# INTAN_Interface.net
KiCad netlist of a schematic drawn in Altium Designer
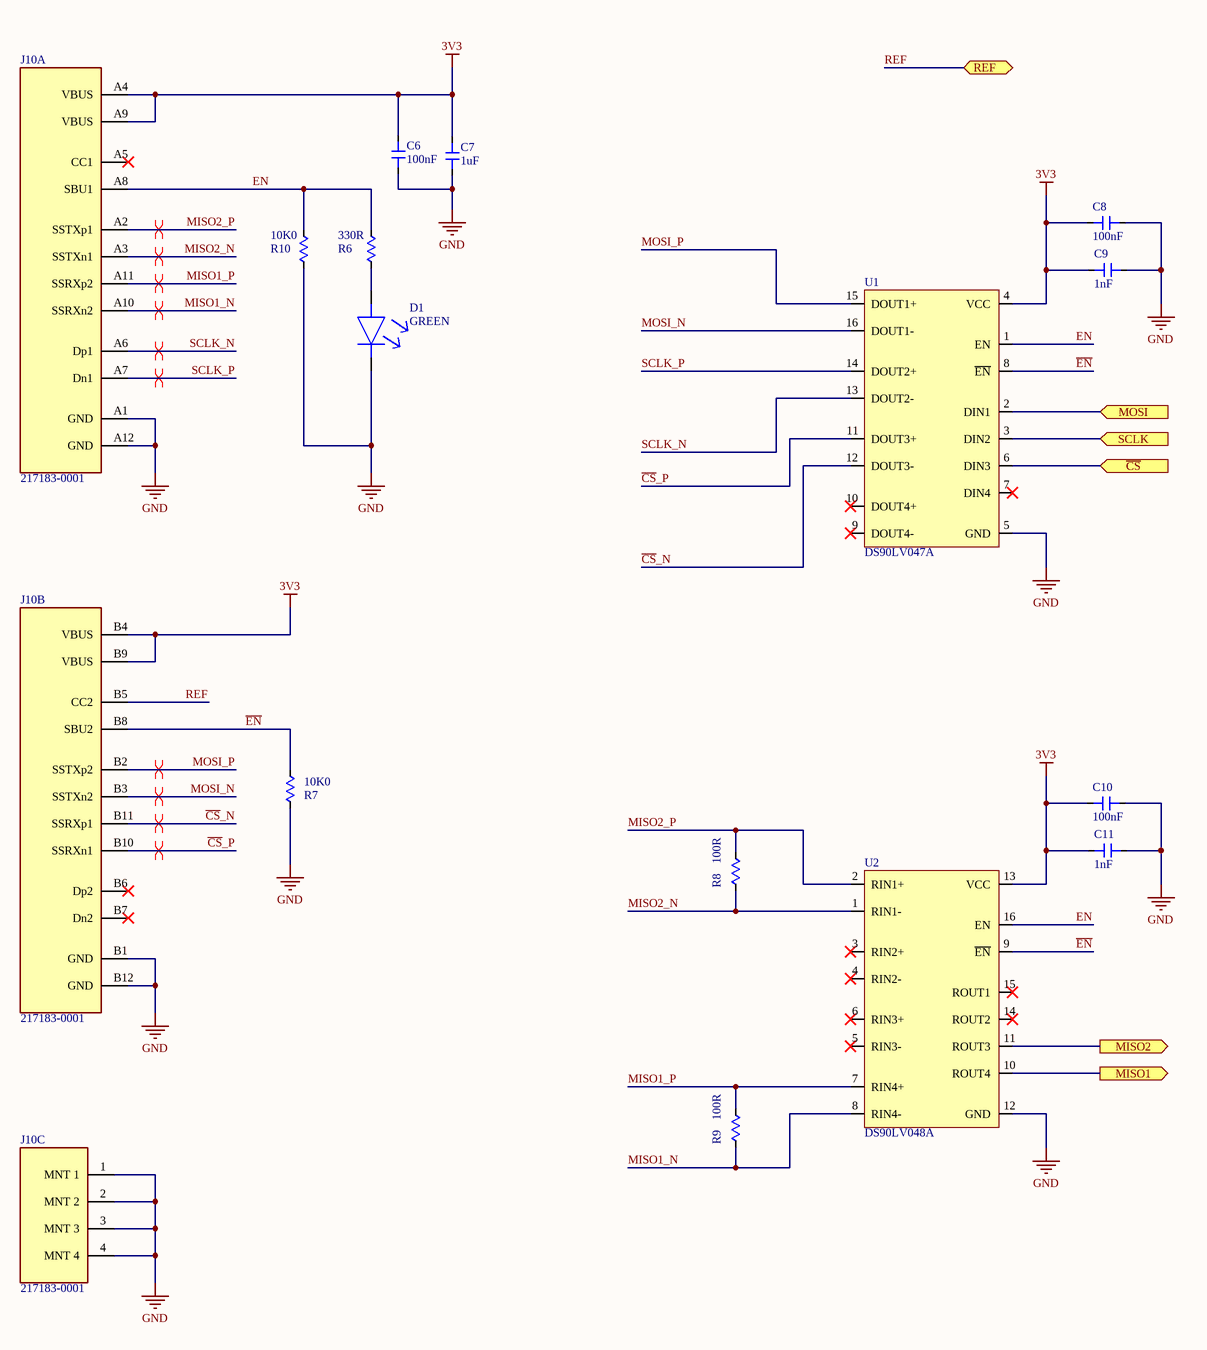
[diagram p0: INTAN_Interface.SchDoc]

(export (version "E")
  (design (tool "Eeschema 10.0.6"))
  (components
    (comp (ref "C6")
      (value "100nF")
      (footprint "0603_CAPACITOR")
      (description "Capacitor")
      (libsource (lib "UHDEMG") (part "Capacitor"))
    )
    (comp (ref "C7")
      (value "1uF")
      (footprint "0603_CAPACITOR")
      (description "Capacitor")
      (libsource (lib "UHDEMG") (part "Capacitor"))
    )
    (comp (ref "C8")
      (value "100nF")
      (footprint "0603_CAPACITOR")
      (description "Capacitor")
      (libsource (lib "UHDEMG") (part "Capacitor"))
    )
    (comp (ref "C9")
      (value "1nF")
      (footprint "0603_CAPACITOR")
      (description "Capacitor")
      (libsource (lib "UHDEMG") (part "Capacitor"))
    )
    (comp (ref "C10")
      (value "100nF")
      (footprint "0603_CAPACITOR")
      (description "Capacitor")
      (libsource (lib "UHDEMG") (part "Capacitor"))
    )
    (comp (ref "C11")
      (value "1nF")
      (footprint "0603_CAPACITOR")
      (description "Capacitor")
      (libsource (lib "UHDEMG") (part "Capacitor"))
    )
    (comp (ref "D1")
      (value "GREEN")
      (footprint "LED_APT1608LZGCK")
      (description "GREEN LED")
      (libsource (lib "UHDEMG") (part "LED_GREEN"))
    )
    (comp (ref "J10")
      (value "217183-0001")
      (footprint "CON_USB_C_SMD")
      (libsource (lib "UHDEMG") (part "CON_USBC_TH_SMT"))
    )
    (comp (ref "R6")
      (value "330R")
      (footprint "0603_RESISTOR")
      (description "Resistor")
      (libsource (lib "UHDEMG") (part "Resistor"))
    )
    (comp (ref "R7")
      (value "10K0")
      (footprint "0603_RESISTOR")
      (description "Resistor")
      (libsource (lib "UHDEMG") (part "Resistor"))
    )
    (comp (ref "R8")
      (value "100R")
      (footprint "0402_Resistor")
      (description "Resistor")
      (libsource (lib "UHDEMG") (part "Resistor"))
    )
    (comp (ref "R9")
      (value "100R")
      (footprint "0402_Resistor")
      (description "Resistor")
      (libsource (lib "UHDEMG") (part "Resistor"))
    )
    (comp (ref "R10")
      (value "10K0")
      (footprint "0603_RESISTOR")
      (description "Resistor")
      (libsource (lib "UHDEMG") (part "Resistor"))
    )
    (comp (ref "U1")
      (value "DS90LV047A")
      (footprint "TTSOP_16")
      (description "LVDS Transceiver 4 Channels with Enable")
      (libsource (lib "UHDEMG") (part "IC_LVDS_TX4"))
    )
    (comp (ref "U2")
      (value "DS90LV048A")
      (footprint "TTSOP_16")
      (description "LVDS Receiver 4 Channels with Enable")
      (libsource (lib "UHDEMG") (part "IC_LVDS_RX4"))
    )
  )
  (nets
    (net (code "1") (name "/EN") (class "Default")
      (node (ref "J10") (pin "A8") (pinfunction "SBU1_A8") (pintype "passive"))
      (node (ref "R10") (pin "2") (pinfunction "2_2") (pintype "passive"))
      (node (ref "R6") (pin "2") (pinfunction "2_2") (pintype "passive"))
      (node (ref "U1") (pin "1") (pinfunction "EN_1") (pintype "passive"))
      (node (ref "U2") (pin "16") (pinfunction "EN_16") (pintype "passive"))
    )
    (net (code "2") (name "/MISO1") (class "Default")
      (node (ref "U2") (pin "10") (pinfunction "ROUT4_10") (pintype "passive"))
    )
    (net (code "3") (name "/MISO1_N") (class "Default")
      (node (ref "J10") (pin "A10") (pinfunction "SSRXn2_A10") (pintype "passive"))
      (node (ref "R9") (pin "1") (pinfunction "1_1") (pintype "passive"))
      (node (ref "U2") (pin "8") (pinfunction "RIN4-_8") (pintype "passive"))
    )
    (net (code "4") (name "/MISO1_P") (class "Default")
      (node (ref "J10") (pin "A11") (pinfunction "SSRXp2_A11") (pintype "passive"))
      (node (ref "R9") (pin "2") (pinfunction "2_2") (pintype "passive"))
      (node (ref "U2") (pin "7") (pinfunction "RIN4+_7") (pintype "passive"))
    )
    (net (code "5") (name "/MISO2") (class "Default")
      (node (ref "U2") (pin "11") (pinfunction "ROUT3_11") (pintype "passive"))
    )
    (net (code "6") (name "/MISO2_N") (class "Default")
      (node (ref "J10") (pin "A3") (pinfunction "SSTXn1_A3") (pintype "passive"))
      (node (ref "R8") (pin "1") (pinfunction "1_1") (pintype "passive"))
      (node (ref "U2") (pin "1") (pinfunction "RIN1-_1") (pintype "passive"))
    )
    (net (code "7") (name "/MISO2_P") (class "Default")
      (node (ref "J10") (pin "A2") (pinfunction "SSTXp1_A2") (pintype "passive"))
      (node (ref "R8") (pin "2") (pinfunction "2_2") (pintype "passive"))
      (node (ref "U2") (pin "2") (pinfunction "RIN1+_2") (pintype "passive"))
    )
    (net (code "8") (name "/MOSI") (class "Default")
      (node (ref "U1") (pin "2") (pinfunction "DIN1_2") (pintype "passive"))
    )
    (net (code "9") (name "/MOSI_N") (class "Default")
      (node (ref "J10") (pin "B3") (pinfunction "SSTXn2_B3") (pintype "passive"))
      (node (ref "U1") (pin "16") (pinfunction "DOUT1-_16") (pintype "passive"))
    )
    (net (code "10") (name "/MOSI_P") (class "Default")
      (node (ref "J10") (pin "B2") (pinfunction "SSTXp2_B2") (pintype "passive"))
      (node (ref "U1") (pin "15") (pinfunction "DOUT1+_15") (pintype "passive"))
    )
    (net (code "11") (name "/REF") (class "Default")
      (node (ref "J10") (pin "B5") (pinfunction "CC2_B5") (pintype "passive"))
    )
    (net (code "12") (name "/SCLK") (class "Default")
      (node (ref "U1") (pin "3") (pinfunction "DIN2_3") (pintype "passive"))
    )
    (net (code "13") (name "/SCLK_N") (class "Default")
      (node (ref "J10") (pin "A6") (pinfunction "Dp1_A6") (pintype "passive"))
      (node (ref "U1") (pin "13") (pinfunction "DOUT2-_13") (pintype "passive"))
    )
    (net (code "14") (name "/SCLK_P") (class "Default")
      (node (ref "J10") (pin "A7") (pinfunction "Dn1_A7") (pintype "passive"))
      (node (ref "U1") (pin "14") (pinfunction "DOUT2+_14") (pintype "passive"))
    )
    (net (code "15") (name "/~{CS}") (class "Default")
      (node (ref "U1") (pin "6") (pinfunction "DIN3_6") (pintype "passive"))
    )
    (net (code "16") (name "/~{CS}_N") (class "Default")
      (node (ref "J10") (pin "B11") (pinfunction "SSRXp1_B11") (pintype "passive"))
      (node (ref "U1") (pin "12") (pinfunction "DOUT3-_12") (pintype "passive"))
    )
    (net (code "17") (name "/~{CS}_P") (class "Default")
      (node (ref "J10") (pin "B10") (pinfunction "SSRXn1_B10") (pintype "passive"))
      (node (ref "U1") (pin "11") (pinfunction "DOUT3+_11") (pintype "passive"))
    )
    (net (code "18") (name "/~{EN}") (class "Default")
      (node (ref "J10") (pin "B8") (pinfunction "SBU2_B8") (pintype "passive"))
      (node (ref "R7") (pin "2") (pinfunction "2_2") (pintype "passive"))
      (node (ref "U1") (pin "8") (pinfunction "~{EN}_8") (pintype "passive"))
      (node (ref "U2") (pin "9") (pinfunction "~{EN}_9") (pintype "passive"))
    )
    (net (code "19") (name "3V3") (class "Default")
      (node (ref "C10") (pin "1") (pinfunction "1_1") (pintype "passive"))
      (node (ref "C11") (pin "1") (pinfunction "1_1") (pintype "passive"))
      (node (ref "C6") (pin "2") (pinfunction "2_2") (pintype "passive"))
      (node (ref "C7") (pin "2") (pinfunction "2_2") (pintype "passive"))
      (node (ref "C8") (pin "1") (pinfunction "1_1") (pintype "passive"))
      (node (ref "C9") (pin "1") (pinfunction "1_1") (pintype "passive"))
      (node (ref "J10") (pin "A4") (pinfunction "VBUS_A4") (pintype "passive"))
      (node (ref "J10") (pin "A9") (pinfunction "VBUS_A9") (pintype "passive"))
      (node (ref "J10") (pin "B4") (pinfunction "VBUS_B4") (pintype "passive"))
      (node (ref "J10") (pin "B9") (pinfunction "VBUS_B9") (pintype "passive"))
      (node (ref "U1") (pin "4") (pinfunction "VCC_4") (pintype "passive"))
      (node (ref "U2") (pin "13") (pinfunction "VCC_13") (pintype "passive"))
    )
    (net (code "20") (name "GND") (class "Default")
      (node (ref "C10") (pin "2") (pinfunction "2_2") (pintype "passive"))
      (node (ref "C11") (pin "2") (pinfunction "2_2") (pintype "passive"))
      (node (ref "C6") (pin "1") (pinfunction "1_1") (pintype "passive"))
      (node (ref "C7") (pin "1") (pinfunction "1_1") (pintype "passive"))
      (node (ref "C8") (pin "2") (pinfunction "2_2") (pintype "passive"))
      (node (ref "C9") (pin "2") (pinfunction "2_2") (pintype "passive"))
      (node (ref "D1") (pin "1") (pinfunction "1_1") (pintype "passive"))
      (node (ref "J10") (pin "1") (pinfunction "MNT_1_1") (pintype "passive"))
      (node (ref "J10") (pin "2") (pinfunction "MNT_2_2") (pintype "passive"))
      (node (ref "J10") (pin "3") (pinfunction "MNT_3_3") (pintype "passive"))
      (node (ref "J10") (pin "4") (pinfunction "MNT_4_4") (pintype "passive"))
      (node (ref "J10") (pin "A1") (pinfunction "GND_A1") (pintype "passive"))
      (node (ref "J10") (pin "A12") (pinfunction "GND_A12") (pintype "passive"))
      (node (ref "J10") (pin "B1") (pinfunction "GND_B1") (pintype "passive"))
      (node (ref "J10") (pin "B12") (pinfunction "GND_B12") (pintype "passive"))
      (node (ref "R10") (pin "1") (pinfunction "1_1") (pintype "passive"))
      (node (ref "R7") (pin "1") (pinfunction "1_1") (pintype "passive"))
      (node (ref "U1") (pin "5") (pinfunction "GND_5") (pintype "passive"))
      (node (ref "U2") (pin "12") (pinfunction "GND_12") (pintype "passive"))
    )
    (net (code "21") (name "Net-(D1-Pad2)") (class "Default")
      (node (ref "D1") (pin "2") (pinfunction "2_2") (pintype "passive"))
      (node (ref "R6") (pin "1") (pinfunction "1_1") (pintype "passive"))
    )
    (net (code "22") (name "unconnected-(J10A-CC1-PadA5)") (class "Default")
      (node (ref "J10") (pin "A5") (pinfunction "CC1_A5") (pintype "passive+no_connect"))
    )
    (net (code "23") (name "unconnected-(J10B-Dn2-PadB7)") (class "Default")
      (node (ref "J10") (pin "B7") (pinfunction "Dn2_B7") (pintype "passive+no_connect"))
    )
    (net (code "24") (name "unconnected-(J10B-Dp2-PadB6)") (class "Default")
      (node (ref "J10") (pin "B6") (pinfunction "Dp2_B6") (pintype "passive+no_connect"))
    )
    (net (code "25") (name "unconnected-(U1-DIN4-Pad7)") (class "Default")
      (node (ref "U1") (pin "7") (pinfunction "DIN4_7") (pintype "passive+no_connect"))
    )
    (net (code "26") (name "unconnected-(U1-DOUT4+-Pad10)") (class "Default")
      (node (ref "U1") (pin "10") (pinfunction "DOUT4+_10") (pintype "passive+no_connect"))
    )
    (net (code "27") (name "unconnected-(U1-DOUT4--Pad9)") (class "Default")
      (node (ref "U1") (pin "9") (pinfunction "DOUT4-_9") (pintype "passive+no_connect"))
    )
    (net (code "28") (name "unconnected-(U2-RIN2+-Pad3)") (class "Default")
      (node (ref "U2") (pin "3") (pinfunction "RIN2+_3") (pintype "passive+no_connect"))
    )
    (net (code "29") (name "unconnected-(U2-RIN2--Pad4)") (class "Default")
      (node (ref "U2") (pin "4") (pinfunction "RIN2-_4") (pintype "passive+no_connect"))
    )
    (net (code "30") (name "unconnected-(U2-RIN3+-Pad6)") (class "Default")
      (node (ref "U2") (pin "6") (pinfunction "RIN3+_6") (pintype "passive+no_connect"))
    )
    (net (code "31") (name "unconnected-(U2-RIN3--Pad5)") (class "Default")
      (node (ref "U2") (pin "5") (pinfunction "RIN3-_5") (pintype "passive+no_connect"))
    )
    (net (code "32") (name "unconnected-(U2-ROUT1-Pad15)") (class "Default")
      (node (ref "U2") (pin "15") (pinfunction "ROUT1_15") (pintype "passive+no_connect"))
    )
    (net (code "33") (name "unconnected-(U2-ROUT2-Pad14)") (class "Default")
      (node (ref "U2") (pin "14") (pinfunction "ROUT2_14") (pintype "passive+no_connect"))
    )
  )
)
